# esp32_usb_c.net
KiCad netlist of a schematic drawn in Altium Designer
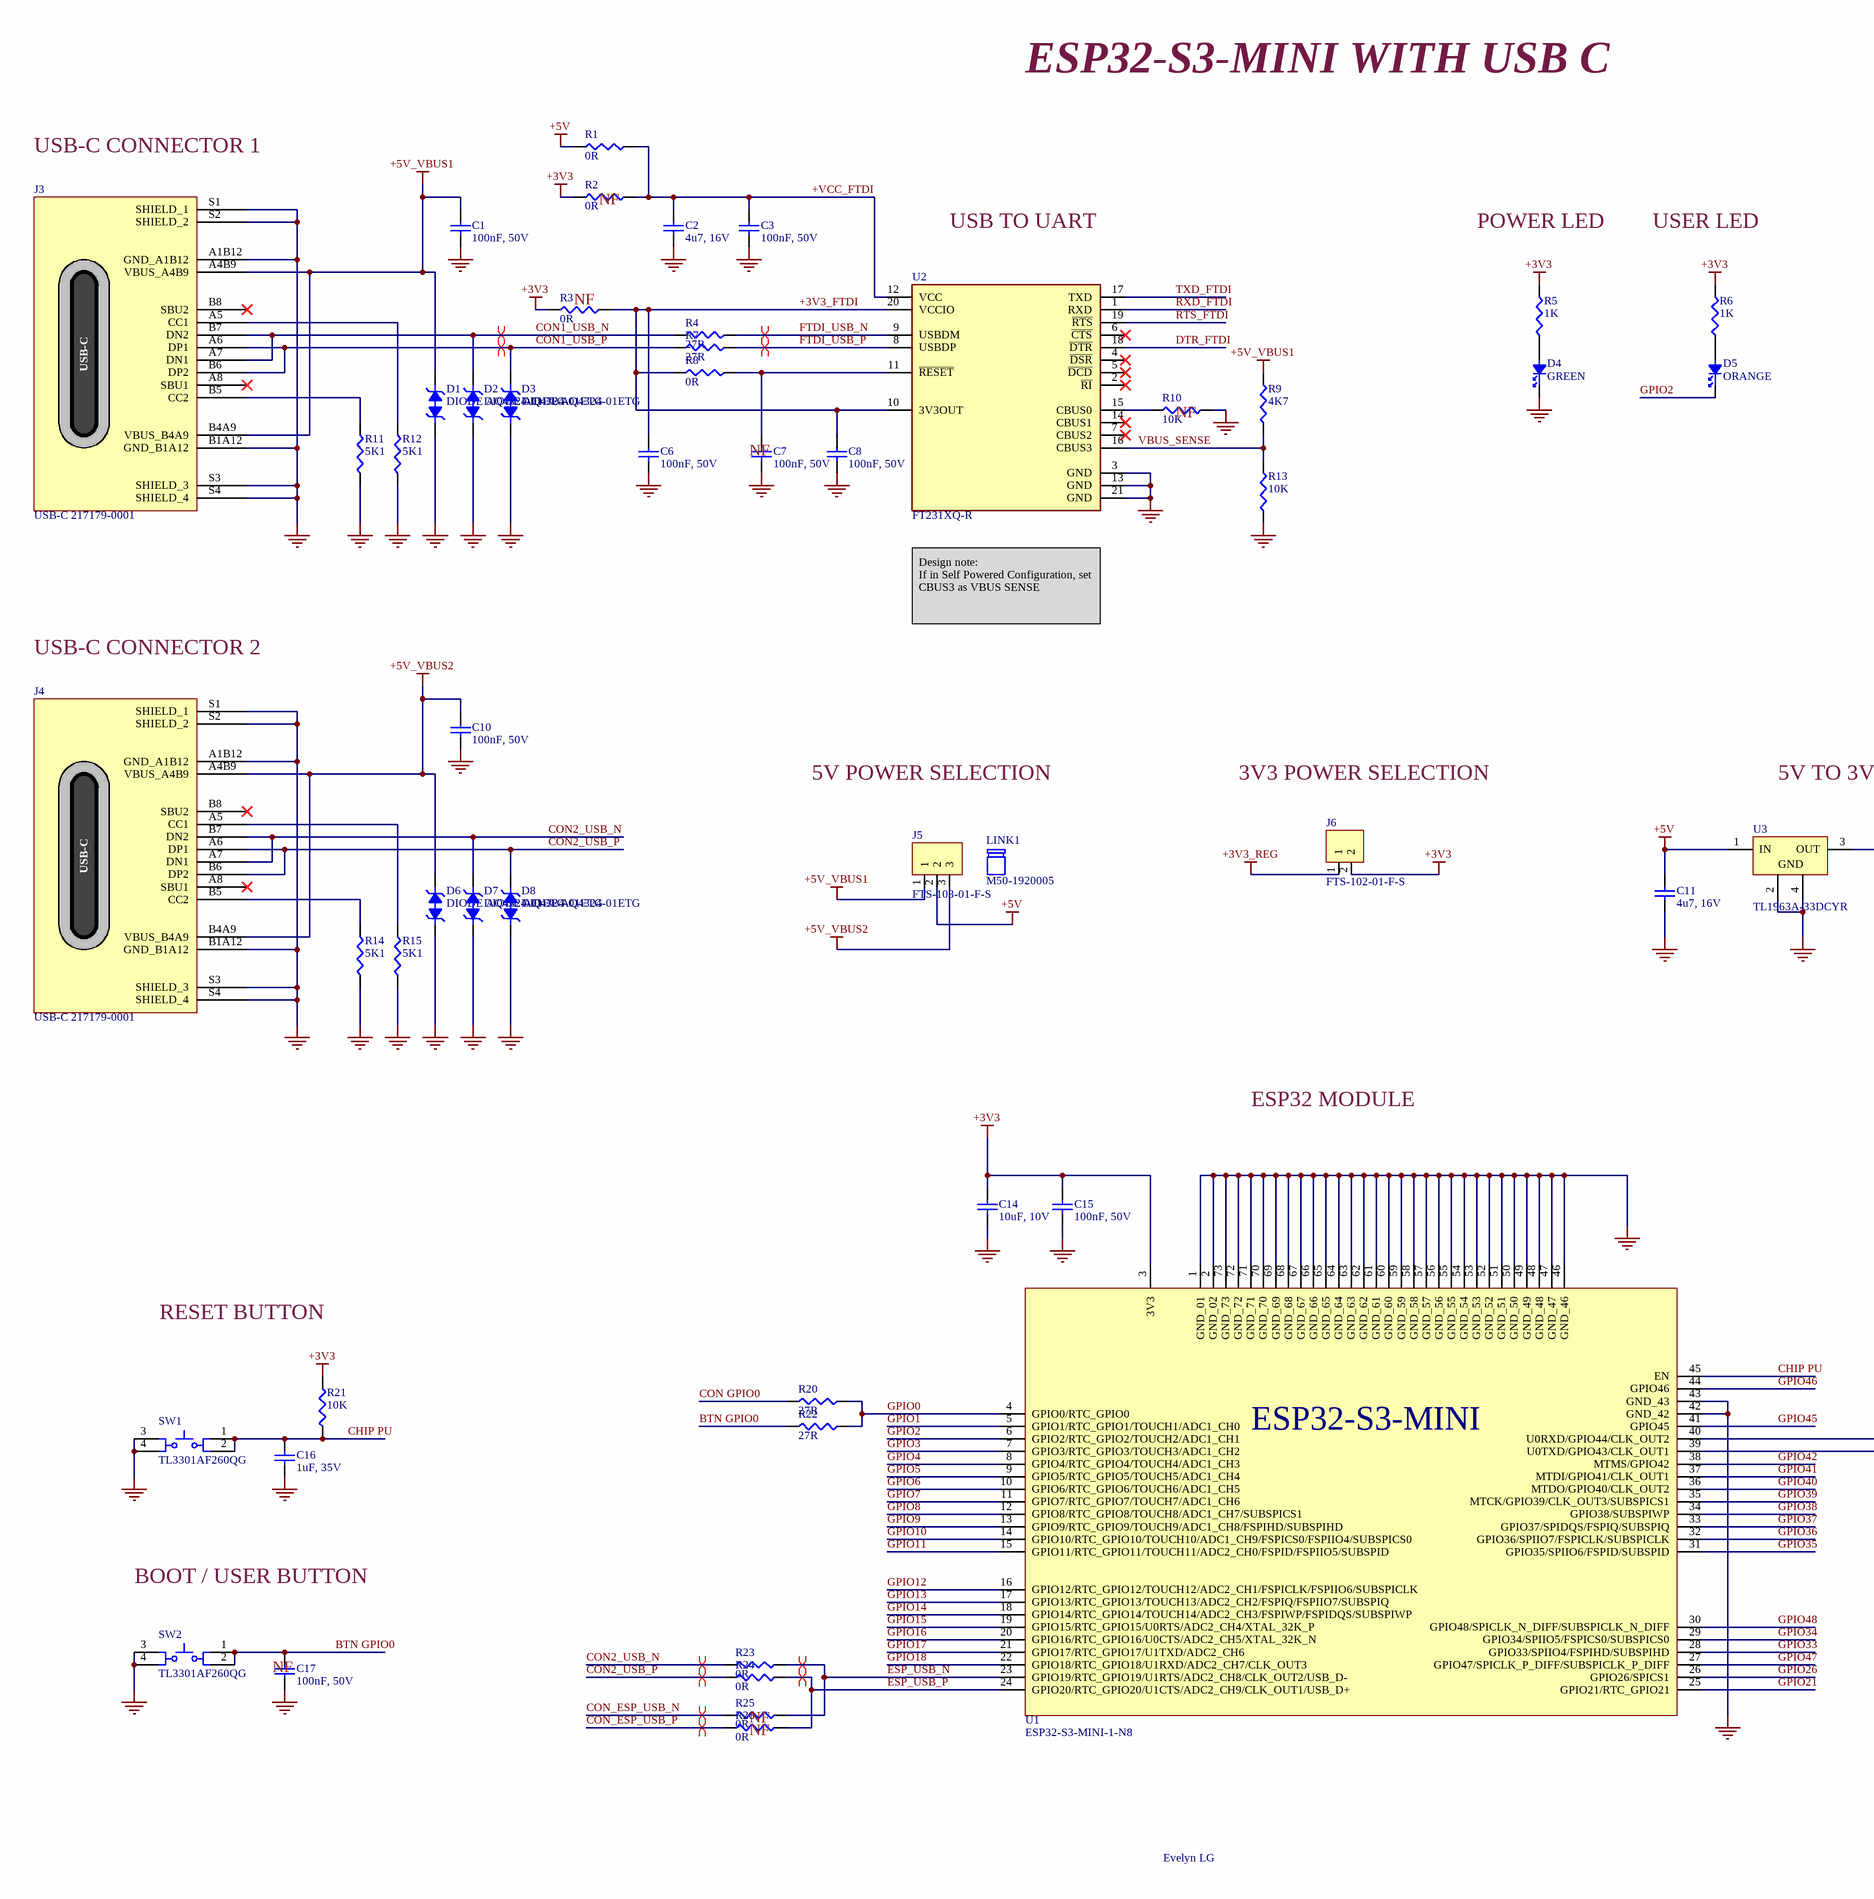
[diagram p0: esp32_usb_c.SchDoc, left]
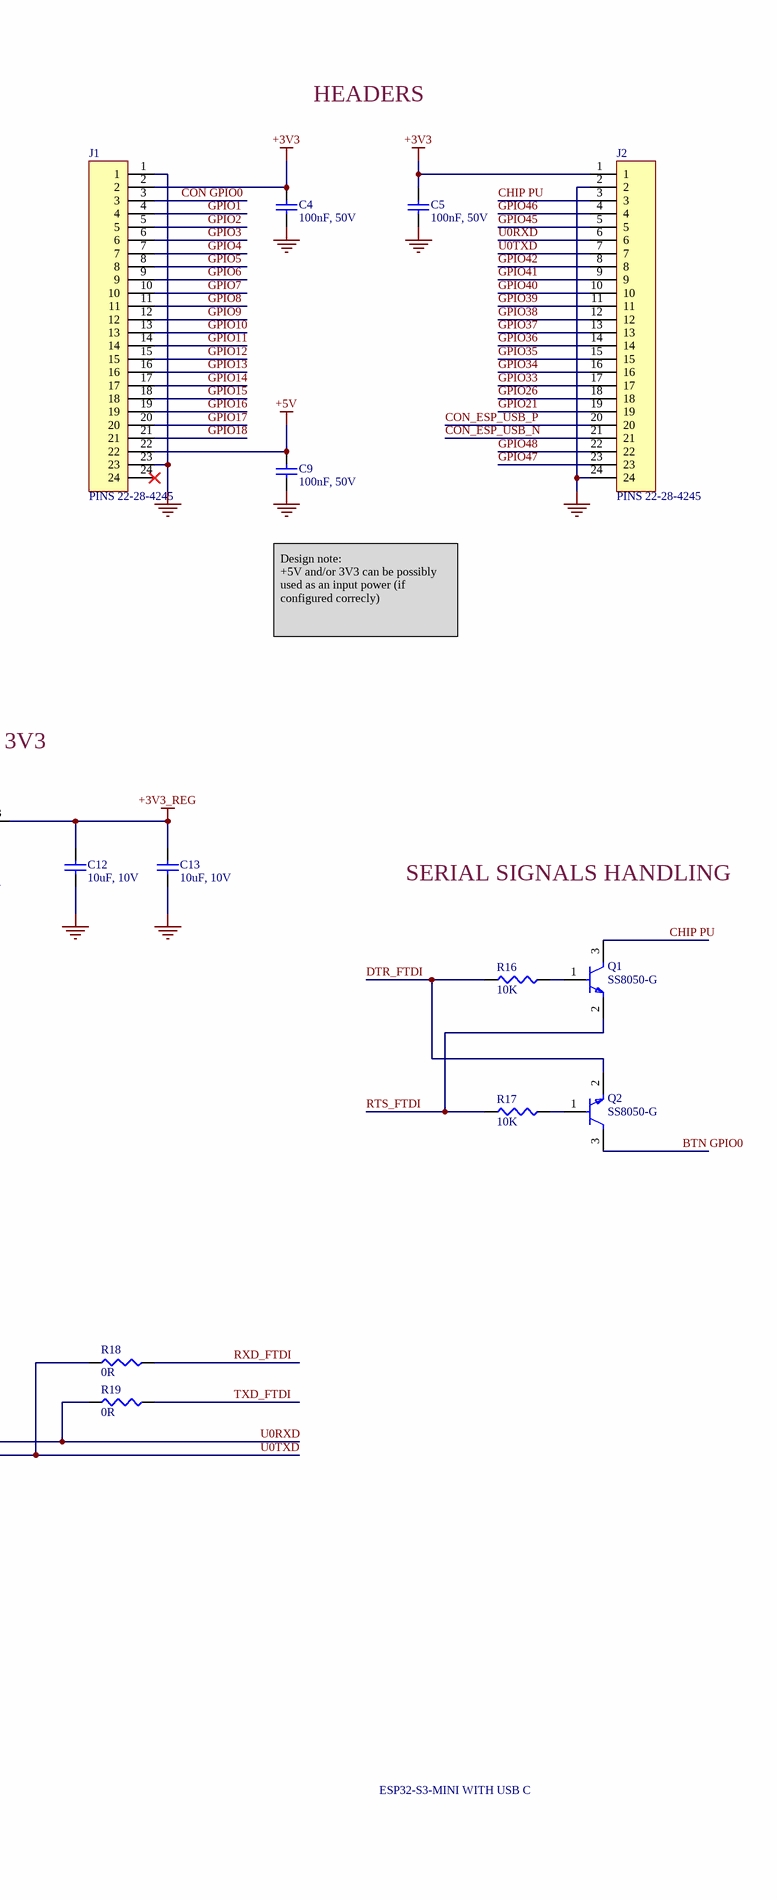
[diagram p1: esp32_usb_c.SchDoc, right]

(export (version "E")
  (design (tool "Eeschema 10.0.6"))
  (components
    (comp (ref "C1")
      (value "100nF, 50V")
      (footprint "CAPC1005X90N")
      (description "CAP CER 0.1UF 50V X7R 0402")
      (fields
        (field (name "MANUFACTURER") "Samsung Electro-Mechanics")
        (field (name "MANUFACTURER PART NUMBER") "CL05B104KB5NNNC")
      )
      (libsource (lib "Schlib") (part "CL05B104KB5NNNC"))
    )
    (comp (ref "C2")
      (value "4u7, 16V")
      (footprint "CAPC1005X90N")
      (description "CAP CER 4.7UF 16V X5R 0402")
      (fields
        (field (name "MANUFACTURER") "Samsung Electro-Mechanics")
        (field (name "MANUFACTURER PART NUMBER") "CL05A475MO5NUNC")
      )
      (libsource (lib "Schlib") (part "CL05A475MO5NUNC"))
    )
    (comp (ref "C3")
      (value "100nF, 50V")
      (footprint "CAPC1005X90N")
      (description "CAP CER 0.1UF 50V X7R 0402")
      (fields
        (field (name "MANUFACTURER") "Samsung Electro-Mechanics")
        (field (name "MANUFACTURER PART NUMBER") "CL05B104KB5NNNC")
      )
      (libsource (lib "Schlib") (part "CL05B104KB5NNNC"))
    )
    (comp (ref "C4")
      (value "100nF, 50V")
      (footprint "CAPC1005X90N")
      (description "CAP CER 0.1UF 50V X7R 0402")
      (fields
        (field (name "MANUFACTURER") "Samsung Electro-Mechanics")
        (field (name "MANUFACTURER PART NUMBER") "CL05B104KB5NNNC")
      )
      (libsource (lib "Schlib") (part "CL05B104KB5NNNC"))
    )
    (comp (ref "C5")
      (value "100nF, 50V")
      (footprint "CAPC1005X90N")
      (description "CAP CER 0.1UF 50V X7R 0402")
      (fields
        (field (name "MANUFACTURER") "Samsung Electro-Mechanics")
        (field (name "MANUFACTURER PART NUMBER") "CL05B104KB5NNNC")
      )
      (libsource (lib "Schlib") (part "CL05B104KB5NNNC"))
    )
    (comp (ref "C6")
      (value "100nF, 50V")
      (footprint "CAPC1005X90N")
      (description "CAP CER 0.1UF 50V X7R 0402")
      (fields
        (field (name "MANUFACTURER") "Samsung Electro-Mechanics")
        (field (name "MANUFACTURER PART NUMBER") "CL05B104KB5NNNC")
      )
      (libsource (lib "Schlib") (part "CL05B104KB5NNNC"))
    )
    (comp (ref "C7")
      (value "100nF, 50V")
      (footprint "CAPC1005X90N")
      (description "CAP CER 0.1UF 50V X7R 0402")
      (fields
        (field (name "MANUFACTURER") "Samsung Electro-Mechanics")
        (field (name "MANUFACTURER PART NUMBER") "CL05B104KB5NNNC")
      )
      (libsource (lib "Schlib") (part "CL05B104KB5NNNC"))
    )
    (comp (ref "C8")
      (value "100nF, 50V")
      (footprint "CAPC1005X90N")
      (description "CAP CER 0.1UF 50V X7R 0402")
      (fields
        (field (name "MANUFACTURER") "Samsung Electro-Mechanics")
        (field (name "MANUFACTURER PART NUMBER") "CL05B104KB5NNNC")
      )
      (libsource (lib "Schlib") (part "CL05B104KB5NNNC"))
    )
    (comp (ref "C9")
      (value "100nF, 50V")
      (footprint "CAPC1005X90N")
      (description "CAP CER 0.1UF 50V X7R 0402")
      (fields
        (field (name "MANUFACTURER") "Samsung Electro-Mechanics")
        (field (name "MANUFACTURER PART NUMBER") "CL05B104KB5NNNC")
      )
      (libsource (lib "Schlib") (part "CL05B104KB5NNNC"))
    )
    (comp (ref "C10")
      (value "100nF, 50V")
      (footprint "CAPC1005X90N")
      (description "CAP CER 0.1UF 50V X7R 0402")
      (fields
        (field (name "MANUFACTURER") "Samsung Electro-Mechanics")
        (field (name "MANUFACTURER PART NUMBER") "CL05B104KB5NNNC")
      )
      (libsource (lib "Schlib") (part "CL05B104KB5NNNC"))
    )
    (comp (ref "C11")
      (value "4u7, 16V")
      (footprint "CAPC1005X90N")
      (description "CAP CER 4.7UF 16V X5R 0402")
      (fields
        (field (name "MANUFACTURER") "Samsung Electro-Mechanics")
        (field (name "MANUFACTURER PART NUMBER") "CL05A475MO5NUNC")
      )
      (libsource (lib "Schlib") (part "CL05A475MO5NUNC"))
    )
    (comp (ref "C12")
      (value "10uF, 10V")
      (footprint "CAPC1005X90N")
      (description "CAP CER 10UF 10V X5R 0402")
      (fields
        (field (name "MANUFACTURER") "Samsung Electro-Mechanics")
        (field (name "MANUFACTURER PART NUMBER") "CL05A106MP8NUB8")
      )
      (libsource (lib "Schlib") (part "CL05A106MP8NUB8"))
    )
    (comp (ref "C13")
      (value "10uF, 10V")
      (footprint "CAPC1005X90N")
      (description "CAP CER 10UF 10V X5R 0402")
      (fields
        (field (name "MANUFACTURER") "Samsung Electro-Mechanics")
        (field (name "MANUFACTURER PART NUMBER") "CL05A106MP8NUB8")
      )
      (libsource (lib "Schlib") (part "CL05A106MP8NUB8"))
    )
    (comp (ref "C14")
      (value "10uF, 10V")
      (footprint "CAPC1005X90N")
      (description "CAP CER 10UF 10V X5R 0402")
      (fields
        (field (name "MANUFACTURER") "Samsung Electro-Mechanics")
        (field (name "MANUFACTURER PART NUMBER") "CL05A106MP8NUB8")
      )
      (libsource (lib "Schlib") (part "CL05A106MP8NUB8"))
    )
    (comp (ref "C15")
      (value "100nF, 50V")
      (footprint "CAPC1005X90N")
      (description "CAP CER 0.1UF 50V X7R 0402")
      (fields
        (field (name "MANUFACTURER") "Samsung Electro-Mechanics")
        (field (name "MANUFACTURER PART NUMBER") "CL05B104KB5NNNC")
      )
      (libsource (lib "Schlib") (part "CL05B104KB5NNNC"))
    )
    (comp (ref "C16")
      (value "1uF, 35V")
      (footprint "CAPC1005X90N")
      (description "CAP CER 1UF 10V X6S 0402")
      (fields
        (field (name "MANUFACTURER") "Samsung Electro-Mechanics")
        (field (name "MANUFACTURER PART NUMBER") "CL05X105KP5NNNC")
      )
      (libsource (lib "Schlib") (part "CL05X105KP5NNNC"))
    )
    (comp (ref "C17")
      (value "100nF, 50V")
      (footprint "CAPC1005X90N")
      (description "CAP CER 0.1UF 50V X7R 0402")
      (fields
        (field (name "MANUFACTURER") "Samsung Electro-Mechanics")
        (field (name "MANUFACTURER PART NUMBER") "CL05B104KB5NNNC")
      )
      (libsource (lib "Schlib") (part "CL05B104KB5NNNC"))
    )
    (comp (ref "D1")
      (value "DIODE AQ4324-01ETG")
      (footprint "SOD882")
      (description "DIODE ARRAYS 1CH 24V 12KV Bidir Tvs SOD882")
      (fields
        (field (name "MANUFACTURER") "Littelfuse")
        (field (name "MANUFACTURER PART NUMBER") "AQ4324-01ETG")
      )
      (libsource (lib "Schlib") (part "AQ4324-01ETG"))
    )
    (comp (ref "D2")
      (value "DIODE AQ4324-01ETG")
      (footprint "SOD882")
      (description "DIODE ARRAYS 1CH 24V 12KV Bidir Tvs SOD882")
      (fields
        (field (name "MANUFACTURER") "Littelfuse")
        (field (name "MANUFACTURER PART NUMBER") "AQ4324-01ETG")
      )
      (libsource (lib "Schlib") (part "AQ4324-01ETG"))
    )
    (comp (ref "D3")
      (value "DIODE AQ4324-01ETG")
      (footprint "SOD882")
      (description "DIODE ARRAYS 1CH 24V 12KV Bidir Tvs SOD882")
      (fields
        (field (name "MANUFACTURER") "Littelfuse")
        (field (name "MANUFACTURER PART NUMBER") "AQ4324-01ETG")
      )
      (libsource (lib "Schlib") (part "AQ4324-01ETG"))
    )
    (comp (ref "D4")
      (value "GREEN")
      (footprint "LED_0402_GREEN")
      (description "LED YLW-GRN 0402 SMD")
      (fields
        (field (name "MANUFACTURER") "Vishay")
        (field (name "MANUFACTURER PART NUMBER") "VLMG1500-GS08")
      )
      (libsource (lib "Schlib") (part "VLMG1500-GS08"))
    )
    (comp (ref "D5")
      (value "ORANGE")
      (footprint "LED_0402_ORANGE")
      (description "LED ORANGE 0402 SMD")
      (fields
        (field (name "MANUFACTURER") "Vishay")
        (field (name "MANUFACTURER PART NUMBER") "VLMO1500-GS08")
      )
      (libsource (lib "Schlib") (part "VLMO1500-GS08"))
    )
    (comp (ref "D6")
      (value "DIODE AQ4324-01ETG")
      (footprint "SOD882")
      (description "DIODE ARRAYS 1CH 24V 12KV Bidir Tvs SOD882")
      (fields
        (field (name "MANUFACTURER") "Littelfuse")
        (field (name "MANUFACTURER PART NUMBER") "AQ4324-01ETG")
      )
      (libsource (lib "Schlib") (part "AQ4324-01ETG"))
    )
    (comp (ref "D7")
      (value "DIODE AQ4324-01ETG")
      (footprint "SOD882")
      (description "DIODE ARRAYS 1CH 24V 12KV Bidir Tvs SOD882")
      (fields
        (field (name "MANUFACTURER") "Littelfuse")
        (field (name "MANUFACTURER PART NUMBER") "AQ4324-01ETG")
      )
      (libsource (lib "Schlib") (part "AQ4324-01ETG"))
    )
    (comp (ref "D8")
      (value "DIODE AQ4324-01ETG")
      (footprint "SOD882")
      (description "DIODE ARRAYS 1CH 24V 12KV Bidir Tvs SOD882")
      (fields
        (field (name "MANUFACTURER") "Littelfuse")
        (field (name "MANUFACTURER PART NUMBER") "AQ4324-01ETG")
      )
      (libsource (lib "Schlib") (part "AQ4324-01ETG"))
    )
    (comp (ref "J1")
      (value "PINS 22-28-4245")
      (footprint "HDR_1X24_2.54MM")
      (description "CONN HEADER VERT 24POS 2.54MM")
      (fields (field (name "MANUFACTURER") "Molex") (field (name "MANUFACTURER PART NUMBER") "22-28-4245"))
      (libsource (lib "Schlib") (part "22-28-4245"))
    )
    (comp (ref "J2")
      (value "PINS 22-28-4245")
      (footprint "HDR_1X24_2.54MM")
      (description "CONN HEADER VERT 24POS 2.54MM")
      (fields (field (name "MANUFACTURER") "Molex") (field (name "MANUFACTURER PART NUMBER") "22-28-4245"))
      (libsource (lib "") (part "22-28-4245_1"))
    )
    (comp (ref "J3")
      (value "USB-C 217179-0001")
      (footprint "FP-2171790001-MFG")
      (description "CONN RCP USB2.0 TYP C 24P SMD RA")
      (fields (field (name "MANUFACTURER") "Molex") (field (name "MANUFACTURER PART NUMBER") "217179-0001"))
      (libsource (lib "Schlib") (part "217179-0001"))
    )
    (comp (ref "J4")
      (value "USB-C 217179-0001")
      (footprint "FP-2171790001-MFG")
      (description "CONN RCP USB2.0 TYP C 24P SMD RA")
      (fields (field (name "MANUFACTURER") "Molex") (field (name "MANUFACTURER PART NUMBER") "217179-0001"))
      (libsource (lib "Schlib") (part "217179-0001"))
    )
    (comp (ref "J5")
      (value "FTS-103-01-F-S")
      (footprint "HDR_1X3_1.27MM")
      (description "CONN HEADER VERT 3POS 1.27MM")
      (fields (field (name "MANUFACTURER") "Samtec") (field (name "LCSC PART NUMBER") "C3333578"))
      (libsource (lib "Schlib") (part "FTS-103-01-F-S"))
    )
    (comp (ref "J6")
      (value "FTS-102-01-F-S")
      (footprint "HDR_1X2_1.27MM")
      (description "CONN HEADER VERT 2POS 1.27MM")
      (fields (field (name "MANUFACTURER") "Samtec") (field (name "LCSC PART NUMBER") "C6045317"))
      (libsource (lib "Schlib") (part "FTS-102-01-F-S"))
    )
    (comp (ref "LINK1")
      (value "M50-1920005")
      (description "CONN SHUNT 1.27MM RED")
      (fields (field (name "MANUFACTURER") "Harwin") (field (name "LCSC PART NUMBER") "C6985646"))
      (libsource (lib "Schlib") (part "M50-1920005"))
    )
    (comp (ref "Q1")
      (value "SS8050-G")
      (footprint "FP-SS8050-G-IPC_B")
      (description "TRANS NPN 25V 1.5A SOT-23-3/r")
      (fields (field (name "MANUFACTURER") "Comchip") (field (name "LCSC PART NUMBER") "C164886"))
      (libsource (lib "Schlib") (part "SS8050-G"))
    )
    (comp (ref "Q2")
      (value "SS8050-G")
      (footprint "FP-SS8050-G-IPC_B")
      (description "TRANS NPN 25V 1.5A SOT-23-3/r")
      (fields (field (name "MANUFACTURER") "Comchip") (field (name "LCSC PART NUMBER") "C164886"))
      (libsource (lib "Schlib") (part "SS8050-G"))
    )
    (comp (ref "R1")
      (value "0R")
      (footprint "RESC1005X37N")
      (description "RES 0 OHM JUMPER 1/16W 0402")
      (fields
        (field (name "MANUFACTURER") "Yageo Group")
        (field (name "MANUFACTURER PART NUMBER") "RC0402JR-070RL")
      )
      (libsource (lib "Schlib") (part "RC0402JR-070RL"))
    )
    (comp (ref "R2")
      (value "0R")
      (footprint "RESC1005X37N")
      (description "RES 0 OHM JUMPER 1/16W 0402")
      (fields
        (field (name "MANUFACTURER") "Yageo Group")
        (field (name "MANUFACTURER PART NUMBER") "RC0402JR-070RL")
      )
      (libsource (lib "Schlib") (part "RC0402JR-070RL"))
    )
    (comp (ref "R3")
      (value "0R")
      (footprint "RESC1005X37N")
      (description "RES 0 OHM JUMPER 1/16W 0402")
      (fields
        (field (name "MANUFACTURER") "Yageo Group")
        (field (name "MANUFACTURER PART NUMBER") "RC0402JR-070RL")
      )
      (libsource (lib "Schlib") (part "RC0402JR-070RL"))
    )
    (comp (ref "R4")
      (value "27R")
      (footprint "RESC1005X37N")
      (description "RES 27 OHM 1% 1/16W 0402")
      (fields
        (field (name "MANUFACTURER") "Yageo Group")
        (field (name "MANUFACTURER PART NUMBER") "RC0402FR-0727RL")
      )
      (libsource (lib "Schlib") (part "RC0402FR-0727RL"))
    )
    (comp (ref "R5")
      (value "1K")
      (footprint "RESC1005X37N")
      (description "RES 1K OHM 1% 1/16W 0402")
      (fields
        (field (name "MANUFACTURER") "Yageo Group")
        (field (name "MANUFACTURER PART NUMBER") "RC0402FR-071KL")
      )
      (libsource (lib "Schlib") (part "RC0402FR-071KL"))
    )
    (comp (ref "R6")
      (value "1K")
      (footprint "RESC1005X37N")
      (description "RES 1K OHM 1% 1/16W 0402")
      (fields
        (field (name "MANUFACTURER") "Yageo Group")
        (field (name "MANUFACTURER PART NUMBER") "RC0402FR-071KL")
      )
      (libsource (lib "Schlib") (part "RC0402FR-071KL"))
    )
    (comp (ref "R7")
      (value "27R")
      (footprint "RESC1005X37N")
      (description "RES 27 OHM 1% 1/16W 0402")
      (fields
        (field (name "MANUFACTURER") "Yageo Group")
        (field (name "MANUFACTURER PART NUMBER") "RC0402FR-0727RL")
      )
      (libsource (lib "Schlib") (part "RC0402FR-0727RL"))
    )
    (comp (ref "R8")
      (value "0R")
      (footprint "RESC1005X37N")
      (description "RES 0 OHM JUMPER 1/16W 0402")
      (fields
        (field (name "MANUFACTURER") "Yageo Group")
        (field (name "MANUFACTURER PART NUMBER") "RC0402JR-070RL")
      )
      (libsource (lib "Schlib") (part "RC0402JR-070RL"))
    )
    (comp (ref "R9")
      (value "4K7")
      (footprint "RESC1005X37N")
      (description "RES 4.7K OHM 1% 1/16W 0402")
      (fields
        (field (name "MANUFACTURER") "Yageo Group")
        (field (name "MANUFACTURER PART NUMBER") "RC0402FR-074K7L")
      )
      (libsource (lib "Schlib") (part "RC0402FR-074K7L"))
    )
    (comp (ref "R10")
      (value "10K")
      (footprint "RESC1005X37N")
      (description "Switch Tactile N.O. SPST Round Button Gull Wing 0.05A 12VDC 100000Cycles 1.96N SMD T/R")
      (fields
        (field (name "MANUFACTURER") "Yageo Group")
        (field (name "MANUFACTURER PART NUMBER") "RC0402FR-0710KL")
      )
      (libsource (lib "Schlib") (part "RC0402FR-0710KL"))
    )
    (comp (ref "R11")
      (value "5K1")
      (footprint "RESC1005X37N")
      (description "RES 5.1K OHM 1% 1/16W 0402")
      (fields
        (field (name "MANUFACTURER") "Yageo Group")
        (field (name "MANUFACTURER PART NUMBER") "RC0402FR-075K1L")
      )
      (libsource (lib "Schlib") (part "RC0402FR-075K1L"))
    )
    (comp (ref "R12")
      (value "5K1")
      (footprint "RESC1005X37N")
      (description "RES 5.1K OHM 1% 1/16W 0402")
      (fields
        (field (name "MANUFACTURER") "Yageo Group")
        (field (name "MANUFACTURER PART NUMBER") "RC0402FR-075K1L")
      )
      (libsource (lib "Schlib") (part "RC0402FR-075K1L"))
    )
    (comp (ref "R13")
      (value "10K")
      (footprint "RESC1005X37N")
      (description "Switch Tactile N.O. SPST Round Button Gull Wing 0.05A 12VDC 100000Cycles 1.96N SMD T/R")
      (fields
        (field (name "MANUFACTURER") "Yageo Group")
        (field (name "MANUFACTURER PART NUMBER") "RC0402FR-0710KL")
      )
      (libsource (lib "Schlib") (part "RC0402FR-0710KL"))
    )
    (comp (ref "R14")
      (value "5K1")
      (footprint "RESC1005X37N")
      (description "RES 5.1K OHM 1% 1/16W 0402")
      (fields
        (field (name "MANUFACTURER") "Yageo Group")
        (field (name "MANUFACTURER PART NUMBER") "RC0402FR-075K1L")
      )
      (libsource (lib "Schlib") (part "RC0402FR-075K1L"))
    )
    (comp (ref "R15")
      (value "5K1")
      (footprint "RESC1005X37N")
      (description "RES 5.1K OHM 1% 1/16W 0402")
      (fields
        (field (name "MANUFACTURER") "Yageo Group")
        (field (name "MANUFACTURER PART NUMBER") "RC0402FR-075K1L")
      )
      (libsource (lib "Schlib") (part "RC0402FR-075K1L"))
    )
    (comp (ref "R16")
      (value "10K")
      (footprint "RESC1005X37N")
      (description "Switch Tactile N.O. SPST Round Button Gull Wing 0.05A 12VDC 100000Cycles 1.96N SMD T/R")
      (fields
        (field (name "MANUFACTURER") "Yageo Group")
        (field (name "MANUFACTURER PART NUMBER") "RC0402FR-0710KL")
      )
      (libsource (lib "Schlib") (part "RC0402FR-0710KL"))
    )
    (comp (ref "R17")
      (value "10K")
      (footprint "RESC1005X37N")
      (description "Switch Tactile N.O. SPST Round Button Gull Wing 0.05A 12VDC 100000Cycles 1.96N SMD T/R")
      (fields
        (field (name "MANUFACTURER") "Yageo Group")
        (field (name "MANUFACTURER PART NUMBER") "RC0402FR-0710KL")
      )
      (libsource (lib "Schlib") (part "RC0402FR-0710KL"))
    )
    (comp (ref "R18")
      (value "0R")
      (footprint "RESC1005X37N")
      (description "RES 0 OHM JUMPER 1/16W 0402")
      (fields
        (field (name "MANUFACTURER") "Yageo Group")
        (field (name "MANUFACTURER PART NUMBER") "RC0402JR-070RL")
      )
      (libsource (lib "Schlib") (part "RC0402JR-070RL"))
    )
    (comp (ref "R19")
      (value "0R")
      (footprint "RESC1005X37N")
      (description "RES 0 OHM JUMPER 1/16W 0402")
      (fields
        (field (name "MANUFACTURER") "Yageo Group")
        (field (name "MANUFACTURER PART NUMBER") "RC0402JR-070RL")
      )
      (libsource (lib "Schlib") (part "RC0402JR-070RL"))
    )
    (comp (ref "R20")
      (value "27R")
      (footprint "RESC1005X37N")
      (description "RES 27 OHM 1% 1/16W 0402")
      (fields
        (field (name "MANUFACTURER") "Yageo Group")
        (field (name "MANUFACTURER PART NUMBER") "RC0402FR-0727RL")
      )
      (libsource (lib "Schlib") (part "RC0402FR-0727RL"))
    )
    (comp (ref "R21")
      (value "10K")
      (footprint "RESC1005X37N")
      (description "Switch Tactile N.O. SPST Round Button Gull Wing 0.05A 12VDC 100000Cycles 1.96N SMD T/R")
      (fields
        (field (name "MANUFACTURER") "Yageo Group")
        (field (name "MANUFACTURER PART NUMBER") "RC0402FR-0710KL")
      )
      (libsource (lib "Schlib") (part "RC0402FR-0710KL"))
    )
    (comp (ref "R22")
      (value "27R")
      (footprint "RESC1005X37N")
      (description "RES 27 OHM 1% 1/16W 0402")
      (fields
        (field (name "MANUFACTURER") "Yageo Group")
        (field (name "MANUFACTURER PART NUMBER") "RC0402FR-0727RL")
      )
      (libsource (lib "Schlib") (part "RC0402FR-0727RL"))
    )
    (comp (ref "R23")
      (value "0R")
      (footprint "RESC1005X37N")
      (description "RES 0 OHM JUMPER 1/16W 0402")
      (fields
        (field (name "MANUFACTURER") "Yageo Group")
        (field (name "MANUFACTURER PART NUMBER") "RC0402JR-070RL")
      )
      (libsource (lib "Schlib") (part "RC0402JR-070RL"))
    )
    (comp (ref "R24")
      (value "0R")
      (footprint "RESC1005X37N")
      (description "RES 0 OHM JUMPER 1/16W 0402")
      (fields
        (field (name "MANUFACTURER") "Yageo Group")
        (field (name "MANUFACTURER PART NUMBER") "RC0402JR-070RL")
      )
      (libsource (lib "Schlib") (part "RC0402JR-070RL"))
    )
    (comp (ref "R25")
      (value "0R")
      (footprint "RESC1005X37N")
      (description "RES 0 OHM JUMPER 1/16W 0402")
      (fields
        (field (name "MANUFACTURER") "Yageo Group")
        (field (name "MANUFACTURER PART NUMBER") "RC0402JR-070RL")
      )
      (libsource (lib "Schlib") (part "RC0402JR-070RL"))
    )
    (comp (ref "R26")
      (value "0R")
      (footprint "RESC1005X37N")
      (description "RES 0 OHM JUMPER 1/16W 0402")
      (fields
        (field (name "MANUFACTURER") "Yageo Group")
        (field (name "MANUFACTURER PART NUMBER") "RC0402JR-070RL")
      )
      (libsource (lib "Schlib") (part "RC0402JR-070RL"))
    )
    (comp (ref "SW1")
      (value "TL3301AF260QG")
      (footprint "ESWI-TL3301AF260QG_V")
      (description "SWITCH TACTILE SPST-NO 0.05A 12V")
      (fields (field (name "MANUFACTURER") "E-Switch") (field (name "LCSC PART #") "C273496"))
      (libsource (lib "Schlib") (part "TL3301AF260QG"))
    )
    (comp (ref "SW2")
      (value "TL3301AF260QG")
      (footprint "ESWI-TL3301AF260QG_V")
      (description "SWITCH TACTILE SPST-NO 0.05A 12V")
      (fields (field (name "MANUFACTURER") "E-Switch") (field (name "LCSC PART #") "C273496"))
      (libsource (lib "Schlib") (part "TL3301AF260QG"))
    )
    (comp (ref "U1")
      (value "ESP32-S3-MINI-1-N8")
      (footprint "XCVR_ESP32-S3-MINI-1-N8")
      (description "20.5dBm ESP32-S3FN8 Chip 2.4GHz SMD WiFi Modules ROHS")
      (fields (field (name "MANUFACTURER") "Espressif Systems") (field (name "LCSC PART NUMBER") "C2913206"))
      (libsource (lib "Schlib") (part "ESP32-S3-MINI-1-N8"))
    )
    (comp (ref "U2")
      (value "FT231XQ-R")
      (footprint "FP-QFN-20-IPC_B")
      (description "IC USB SERIAL FULL UART 20QFN")
      (fields (field (name "MANUFACTURER") "FTDI") (field (name "LCSC PART NUMBER") "C132159"))
      (libsource (lib "Schlib") (part "FT231XQ-R"))
    )
    (comp (ref "U3")
      (value "TL1963A-33DCYR")
      (footprint "DCY0004A_N")
      (description "IC REG LIN 3.3V 1.5A SOT-223-4")
      (fields (field (name "MANUFACTURER") "Texas Instruments") (field (name "LCSC PART NUMBER") "C181262"))
      (libsource (lib "Schlib") (part "TL1963A-33DCYR"))
    )
  )
  (nets
    (net (code "1") (name "+3V3") (class "Default")
      (node (ref "C14") (pin "2") (pinfunction "2_2") (pintype "passive"))
      (node (ref "C15") (pin "2") (pinfunction "2_2") (pintype "passive"))
      (node (ref "C4") (pin "2") (pinfunction "2_2") (pintype "passive"))
      (node (ref "C5") (pin "2") (pinfunction "2_2") (pintype "passive"))
      (node (ref "J1") (pin "2") (pinfunction "2_2") (pintype "passive"))
      (node (ref "J2") (pin "1") (pinfunction "1_1") (pintype "passive"))
      (node (ref "J6") (pin "2") (pinfunction "2_2") (pintype "passive"))
      (node (ref "R2") (pin "1") (pinfunction "1_1") (pintype "passive"))
      (node (ref "R21") (pin "2") (pinfunction "2_2") (pintype "passive"))
      (node (ref "R3") (pin "1") (pinfunction "1_1") (pintype "passive"))
      (node (ref "R5") (pin "2") (pinfunction "2_2") (pintype "passive"))
      (node (ref "R6") (pin "2") (pinfunction "2_2") (pintype "passive"))
      (node (ref "U1") (pin "3") (pinfunction "3V3_3") (pintype "passive"))
    )
    (net (code "2") (name "+3V3_REG") (class "Default")
      (node (ref "C12") (pin "2") (pinfunction "2_2") (pintype "passive"))
      (node (ref "C13") (pin "2") (pinfunction "2_2") (pintype "passive"))
      (node (ref "J6") (pin "1") (pinfunction "1_1") (pintype "passive"))
      (node (ref "U3") (pin "3") (pinfunction "OUT_3") (pintype "power_in"))
    )
    (net (code "3") (name "+5V") (class "Default")
      (node (ref "C11") (pin "2") (pinfunction "2_2") (pintype "passive"))
      (node (ref "C9") (pin "2") (pinfunction "2_2") (pintype "passive"))
      (node (ref "J1") (pin "22") (pinfunction "22_22") (pintype "passive"))
      (node (ref "J5") (pin "2") (pinfunction "2_2") (pintype "passive"))
      (node (ref "R1") (pin "1") (pinfunction "1_1") (pintype "passive"))
      (node (ref "U3") (pin "1") (pinfunction "IN_1") (pintype "power_in"))
    )
    (net (code "4") (name "+5V_VBUS1") (class "Default")
      (node (ref "C1") (pin "2") (pinfunction "2_2") (pintype "passive"))
      (node (ref "D1") (pin "2") (pinfunction "2_2") (pintype "passive"))
      (node (ref "J3") (pin "A4B9") (pinfunction "VBUS_A4B9_A4B9") (pintype "passive"))
      (node (ref "J3") (pin "B4A9") (pinfunction "VBUS_B4A9_B4A9") (pintype "passive"))
      (node (ref "J5") (pin "1") (pinfunction "1_1") (pintype "passive"))
      (node (ref "R9") (pin "2") (pinfunction "2_2") (pintype "passive"))
    )
    (net (code "5") (name "+5V_VBUS2") (class "Default")
      (node (ref "C10") (pin "2") (pinfunction "2_2") (pintype "passive"))
      (node (ref "D6") (pin "2") (pinfunction "2_2") (pintype "passive"))
      (node (ref "J4") (pin "A4B9") (pinfunction "VBUS_A4B9_A4B9") (pintype "passive"))
      (node (ref "J4") (pin "B4A9") (pinfunction "VBUS_B4A9_B4A9") (pintype "passive"))
      (node (ref "J5") (pin "3") (pinfunction "3_3") (pintype "passive"))
    )
    (net (code "6") (name "/+3V3_FTDI") (class "Default")
      (node (ref "C6") (pin "2") (pinfunction "2_2") (pintype "passive"))
      (node (ref "C8") (pin "2") (pinfunction "2_2") (pintype "passive"))
      (node (ref "R3") (pin "2") (pinfunction "2_2") (pintype "passive"))
      (node (ref "R8") (pin "1") (pinfunction "1_1") (pintype "passive"))
      (node (ref "U2") (pin "10") (pinfunction "3V3OUT_10") (pintype "passive"))
      (node (ref "U2") (pin "20") (pinfunction "VCCIO_20") (pintype "passive"))
    )
    (net (code "7") (name "/+VCC_FTDI") (class "Default")
      (node (ref "C2") (pin "2") (pinfunction "2_2") (pintype "passive"))
      (node (ref "C3") (pin "2") (pinfunction "2_2") (pintype "passive"))
      (node (ref "R1") (pin "2") (pinfunction "2_2") (pintype "passive"))
      (node (ref "R2") (pin "2") (pinfunction "2_2") (pintype "passive"))
      (node (ref "U2") (pin "12") (pinfunction "VCC_12") (pintype "passive"))
    )
    (net (code "8") (name "/BTN GPIO0") (class "Default")
      (node (ref "C17") (pin "2") (pinfunction "2_2") (pintype "passive"))
      (node (ref "Q2") (pin "3") (pinfunction "C_3") (pintype "passive"))
      (node (ref "R22") (pin "1") (pinfunction "1_1") (pintype "passive"))
      (node (ref "SW2") (pin "1") (pinfunction "1_1") (pintype "passive"))
      (node (ref "SW2") (pin "2") (pinfunction "2_2") (pintype "passive"))
    )
    (net (code "9") (name "/CHIP PU") (class "Default")
      (node (ref "C16") (pin "2") (pinfunction "2_2") (pintype "passive"))
      (node (ref "J2") (pin "3") (pinfunction "3_3") (pintype "passive"))
      (node (ref "Q1") (pin "3") (pinfunction "C_3") (pintype "passive"))
      (node (ref "R21") (pin "1") (pinfunction "1_1") (pintype "passive"))
      (node (ref "SW1") (pin "1") (pinfunction "1_1") (pintype "passive"))
      (node (ref "SW1") (pin "2") (pinfunction "2_2") (pintype "passive"))
      (node (ref "U1") (pin "45") (pinfunction "EN_45") (pintype "passive"))
    )
    (net (code "10") (name "/CON GPIO0") (class "Default")
      (node (ref "J1") (pin "3") (pinfunction "3_3") (pintype "passive"))
      (node (ref "R20") (pin "1") (pinfunction "1_1") (pintype "passive"))
    )
    (net (code "11") (name "/CON1_USB_N") (class "Default")
      (node (ref "D2") (pin "2") (pinfunction "2_2") (pintype "passive"))
      (node (ref "J3") (pin "A7") (pinfunction "DN1_A7") (pintype "passive"))
      (node (ref "J3") (pin "B7") (pinfunction "DN2_B7") (pintype "passive"))
      (node (ref "R4") (pin "1") (pinfunction "1_1") (pintype "passive"))
    )
    (net (code "12") (name "/CON1_USB_P") (class "Default")
      (node (ref "D3") (pin "2") (pinfunction "2_2") (pintype "passive"))
      (node (ref "J3") (pin "A6") (pinfunction "DP1_A6") (pintype "passive"))
      (node (ref "J3") (pin "B6") (pinfunction "DP2_B6") (pintype "passive"))
      (node (ref "R7") (pin "1") (pinfunction "1_1") (pintype "passive"))
    )
    (net (code "13") (name "/CON2_USB_N") (class "Default")
      (node (ref "D7") (pin "2") (pinfunction "2_2") (pintype "passive"))
      (node (ref "J4") (pin "A7") (pinfunction "DN1_A7") (pintype "passive"))
      (node (ref "J4") (pin "B7") (pinfunction "DN2_B7") (pintype "passive"))
      (node (ref "R23") (pin "1") (pinfunction "1_1") (pintype "passive"))
    )
    (net (code "14") (name "/CON2_USB_P") (class "Default")
      (node (ref "D8") (pin "2") (pinfunction "2_2") (pintype "passive"))
      (node (ref "J4") (pin "A6") (pinfunction "DP1_A6") (pintype "passive"))
      (node (ref "J4") (pin "B6") (pinfunction "DP2_B6") (pintype "passive"))
      (node (ref "R24") (pin "1") (pinfunction "1_1") (pintype "passive"))
    )
    (net (code "15") (name "/CON_ESP_USB_N") (class "Default")
      (node (ref "J2") (pin "21") (pinfunction "21_21") (pintype "passive"))
      (node (ref "R25") (pin "1") (pinfunction "1_1") (pintype "passive"))
    )
    (net (code "16") (name "/CON_ESP_USB_P") (class "Default")
      (node (ref "J2") (pin "20") (pinfunction "20_20") (pintype "passive"))
      (node (ref "R26") (pin "1") (pinfunction "1_1") (pintype "passive"))
    )
    (net (code "17") (name "/DTR_FTDI") (class "Default")
      (node (ref "Q2") (pin "2") (pinfunction "E_2") (pintype "passive"))
      (node (ref "R16") (pin "1") (pinfunction "1_1") (pintype "passive"))
      (node (ref "U2") (pin "18") (pinfunction "~{DTR}_18") (pintype "passive"))
    )
    (net (code "18") (name "/ESP_USB_N") (class "Default")
      (node (ref "R23") (pin "2") (pinfunction "2_2") (pintype "passive"))
      (node (ref "R25") (pin "2") (pinfunction "2_2") (pintype "passive"))
      (node (ref "U1") (pin "23") (pinfunction "GPIO19/RTC_GPIO19/U1RTS/ADC2_CH8/CLK_OUT2/USB_D-_23") (pintype "passive"))
    )
    (net (code "19") (name "/ESP_USB_P") (class "Default")
      (node (ref "R24") (pin "2") (pinfunction "2_2") (pintype "passive"))
      (node (ref "R26") (pin "2") (pinfunction "2_2") (pintype "passive"))
      (node (ref "U1") (pin "24") (pinfunction "GPIO20/RTC_GPIO20/U1CTS/ADC2_CH9/CLK_OUT1/USB_D+_24") (pintype "passive"))
    )
    (net (code "20") (name "/FTDI_USB_N") (class "Default")
      (node (ref "R4") (pin "2") (pinfunction "2_2") (pintype "passive"))
      (node (ref "U2") (pin "9") (pinfunction "USBDM_9") (pintype "passive"))
    )
    (net (code "21") (name "/FTDI_USB_P") (class "Default")
      (node (ref "R7") (pin "2") (pinfunction "2_2") (pintype "passive"))
      (node (ref "U2") (pin "8") (pinfunction "USBDP_8") (pintype "passive"))
    )
    (net (code "22") (name "/GPIO0") (class "Default")
      (node (ref "R20") (pin "2") (pinfunction "2_2") (pintype "passive"))
      (node (ref "R22") (pin "2") (pinfunction "2_2") (pintype "passive"))
      (node (ref "U1") (pin "4") (pinfunction "GPIO0/RTC_GPIO0_4") (pintype "passive"))
    )
    (net (code "23") (name "/GPIO1") (class "Default")
      (node (ref "J1") (pin "4") (pinfunction "4_4") (pintype "passive"))
      (node (ref "U1") (pin "5") (pinfunction "GPIO1/RTC_GPIO1/TOUCH1/ADC1_CH0_5") (pintype "passive"))
    )
    (net (code "24") (name "/GPIO2") (class "Default")
      (node (ref "D5") (pin "1") (pinfunction "1_1") (pintype "passive"))
      (node (ref "J1") (pin "5") (pinfunction "5_5") (pintype "passive"))
      (node (ref "U1") (pin "6") (pinfunction "GPIO2/RTC_GPIO2/TOUCH2/ADC1_CH1_6") (pintype "passive"))
    )
    (net (code "25") (name "/GPIO3") (class "Default")
      (node (ref "J1") (pin "6") (pinfunction "6_6") (pintype "passive"))
      (node (ref "U1") (pin "7") (pinfunction "GPIO3/RTC_GPIO3/TOUCH3/ADC1_CH2_7") (pintype "passive"))
    )
    (net (code "26") (name "/GPIO4") (class "Default")
      (node (ref "J1") (pin "7") (pinfunction "7_7") (pintype "passive"))
      (node (ref "U1") (pin "8") (pinfunction "GPIO4/RTC_GPIO4/TOUCH4/ADC1_CH3_8") (pintype "passive"))
    )
    (net (code "27") (name "/GPIO5") (class "Default")
      (node (ref "J1") (pin "8") (pinfunction "8_8") (pintype "passive"))
      (node (ref "U1") (pin "9") (pinfunction "GPIO5/RTC_GPIO5/TOUCH5/ADC1_CH4_9") (pintype "passive"))
    )
    (net (code "28") (name "/GPIO6") (class "Default")
      (node (ref "J1") (pin "9") (pinfunction "9_9") (pintype "passive"))
      (node (ref "U1") (pin "10") (pinfunction "GPIO6/RTC_GPIO6/TOUCH6/ADC1_CH5_10") (pintype "passive"))
    )
    (net (code "29") (name "/GPIO7") (class "Default")
      (node (ref "J1") (pin "10") (pinfunction "10_10") (pintype "passive"))
      (node (ref "U1") (pin "11") (pinfunction "GPIO7/RTC_GPIO7/TOUCH7/ADC1_CH6_11") (pintype "passive"))
    )
    (net (code "30") (name "/GPIO8") (class "Default")
      (node (ref "J1") (pin "11") (pinfunction "11_11") (pintype "passive"))
      (node (ref "U1") (pin "12") (pinfunction "GPIO8/RTC_GPIO8/TOUCH8/ADC1_CH7/SUBSPICS1_12") (pintype "passive"))
    )
    (net (code "31") (name "/GPIO9") (class "Default")
      (node (ref "J1") (pin "12") (pinfunction "12_12") (pintype "passive"))
      (node (ref "U1") (pin "13") (pinfunction "GPIO9/RTC_GPIO9/TOUCH9/ADC1_CH8/FSPIHD/SUBSPIHD_13") (pintype "passive"))
    )
    (net (code "32") (name "/GPIO10") (class "Default")
      (node (ref "J1") (pin "13") (pinfunction "13_13") (pintype "passive"))
      (node (ref "U1") (pin "14") (pinfunction "GPIO10/RTC_GPIO10/TOUCH10/ADC1_CH9/FSPICS0/FSPIIO4/SUBSPICS0_14") (pintype "passive"))
    )
    (net (code "33") (name "/GPIO11") (class "Default")
      (node (ref "J1") (pin "14") (pinfunction "14_14") (pintype "passive"))
      (node (ref "U1") (pin "15") (pinfunction "GPIO11/RTC_GPIO11/TOUCH11/ADC2_CH0/FSPID/FSPIIO5/SUBSPID_15") (pintype "passive"))
    )
    (net (code "34") (name "/GPIO12") (class "Default")
      (node (ref "J1") (pin "15") (pinfunction "15_15") (pintype "passive"))
      (node (ref "U1") (pin "16") (pinfunction "GPIO12/RTC_GPIO12/TOUCH12/ADC2_CH1/FSPICLK/FSPIIO6/SUBSPICLK_16") (pintype "passive"))
    )
    (net (code "35") (name "/GPIO13") (class "Default")
      (node (ref "J1") (pin "16") (pinfunction "16_16") (pintype "passive"))
      (node (ref "U1") (pin "17") (pinfunction "GPIO13/RTC_GPIO13/TOUCH13/ADC2_CH2/FSPIQ/FSPIIO7/SUBSPIQ_17") (pintype "passive"))
    )
    (net (code "36") (name "/GPIO14") (class "Default")
      (node (ref "J1") (pin "17") (pinfunction "17_17") (pintype "passive"))
      (node (ref "U1") (pin "18") (pinfunction "GPIO14/RTC_GPIO14/TOUCH14/ADC2_CH3/FSPIWP/FSPIDQS/SUBSPIWP_18") (pintype "passive"))
    )
    (net (code "37") (name "/GPIO15") (class "Default")
      (node (ref "J1") (pin "18") (pinfunction "18_18") (pintype "passive"))
      (node (ref "U1") (pin "19") (pinfunction "GPIO15/RTC_GPIO15/U0RTS/ADC2_CH4/XTAL_32K_P_19") (pintype "passive"))
    )
    (net (code "38") (name "/GPIO16") (class "Default")
      (node (ref "J1") (pin "19") (pinfunction "19_19") (pintype "passive"))
      (node (ref "U1") (pin "20") (pinfunction "GPIO16/RTC_GPIO16/U0CTS/ADC2_CH5/XTAL_32K_N_20") (pintype "passive"))
    )
    (net (code "39") (name "/GPIO17") (class "Default")
      (node (ref "J1") (pin "20") (pinfunction "20_20") (pintype "passive"))
      (node (ref "U1") (pin "21") (pinfunction "GPIO17/RTC_GPIO17/U1TXD/ADC2_CH6_21") (pintype "passive"))
    )
    (net (code "40") (name "/GPIO18") (class "Default")
      (node (ref "J1") (pin "21") (pinfunction "21_21") (pintype "passive"))
      (node (ref "U1") (pin "22") (pinfunction "GPIO18/RTC_GPIO18/U1RXD/ADC2_CH7/CLK_OUT3_22") (pintype "passive"))
    )
    (net (code "41") (name "/GPIO21") (class "Default")
      (node (ref "J2") (pin "19") (pinfunction "19_19") (pintype "passive"))
      (node (ref "U1") (pin "25") (pinfunction "GPIO21/RTC_GPIO21_25") (pintype "passive"))
    )
    (net (code "42") (name "/GPIO26") (class "Default")
      (node (ref "J2") (pin "18") (pinfunction "18_18") (pintype "passive"))
      (node (ref "U1") (pin "26") (pinfunction "GPIO26/SPICS1_26") (pintype "passive"))
    )
    (net (code "43") (name "/GPIO33") (class "Default")
      (node (ref "J2") (pin "17") (pinfunction "17_17") (pintype "passive"))
      (node (ref "U1") (pin "28") (pinfunction "GPIO33/SPIIO4/FSPIHD/SUBSPIHD_28") (pintype "passive"))
    )
    (net (code "44") (name "/GPIO34") (class "Default")
      (node (ref "J2") (pin "16") (pinfunction "16_16") (pintype "passive"))
      (node (ref "U1") (pin "29") (pinfunction "GPIO34/SPIIO5/FSPICS0/SUBSPICS0_29") (pintype "passive"))
    )
    (net (code "45") (name "/GPIO35") (class "Default")
      (node (ref "J2") (pin "15") (pinfunction "15_15") (pintype "passive"))
      (node (ref "U1") (pin "31") (pinfunction "GPIO35/SPIIO6/FSPID/SUBSPID_31") (pintype "passive"))
    )
    (net (code "46") (name "/GPIO36") (class "Default")
      (node (ref "J2") (pin "14") (pinfunction "14_14") (pintype "passive"))
      (node (ref "U1") (pin "32") (pinfunction "GPIO36/SPIIO7/FSPICLK/SUBSPICLK_32") (pintype "passive"))
    )
    (net (code "47") (name "/GPIO37") (class "Default")
      (node (ref "J2") (pin "13") (pinfunction "13_13") (pintype "passive"))
      (node (ref "U1") (pin "33") (pinfunction "GPIO37/SPIDQS/FSPIQ/SUBSPIQ_33") (pintype "passive"))
    )
    (net (code "48") (name "/GPIO38") (class "Default")
      (node (ref "J2") (pin "12") (pinfunction "12_12") (pintype "passive"))
      (node (ref "U1") (pin "34") (pinfunction "GPIO38/SUBSPIWP_34") (pintype "passive"))
    )
    (net (code "49") (name "/GPIO39") (class "Default")
      (node (ref "J2") (pin "11") (pinfunction "11_11") (pintype "passive"))
      (node (ref "U1") (pin "35") (pinfunction "MTCK/GPIO39/CLK_OUT3/SUBSPICS1_35") (pintype "passive"))
    )
    (net (code "50") (name "/GPIO40") (class "Default")
      (node (ref "J2") (pin "10") (pinfunction "10_10") (pintype "passive"))
      (node (ref "U1") (pin "36") (pinfunction "MTDO/GPIO40/CLK_OUT2_36") (pintype "passive"))
    )
    (net (code "51") (name "/GPIO41") (class "Default")
      (node (ref "J2") (pin "9") (pinfunction "9_9") (pintype "passive"))
      (node (ref "U1") (pin "37") (pinfunction "MTDI/GPIO41/CLK_OUT1_37") (pintype "passive"))
    )
    (net (code "52") (name "/GPIO42") (class "Default")
      (node (ref "J2") (pin "8") (pinfunction "8_8") (pintype "passive"))
      (node (ref "U1") (pin "38") (pinfunction "MTMS/GPIO42_38") (pintype "passive"))
    )
    (net (code "53") (name "/GPIO45") (class "Default")
      (node (ref "J2") (pin "5") (pinfunction "5_5") (pintype "passive"))
      (node (ref "U1") (pin "41") (pinfunction "GPIO45_41") (pintype "passive"))
    )
    (net (code "54") (name "/GPIO46") (class "Default")
      (node (ref "J2") (pin "4") (pinfunction "4_4") (pintype "passive"))
      (node (ref "U1") (pin "44") (pinfunction "GPIO46_44") (pintype "passive"))
    )
    (net (code "55") (name "/GPIO47") (class "Default")
      (node (ref "J2") (pin "23") (pinfunction "23_23") (pintype "passive"))
      (node (ref "U1") (pin "27") (pinfunction "GPIO47/SPICLK_P_DIFF/SUBSPICLK_P_DIFF_27") (pintype "passive"))
    )
    (net (code "56") (name "/GPIO48") (class "Default")
      (node (ref "J2") (pin "22") (pinfunction "22_22") (pintype "passive"))
      (node (ref "U1") (pin "30") (pinfunction "GPIO48/SPICLK_N_DIFF/SUBSPICLK_N_DIFF_30") (pintype "passive"))
    )
    (net (code "57") (name "/RTS_FTDI") (class "Default")
      (node (ref "Q1") (pin "2") (pinfunction "E_2") (pintype "passive"))
      (node (ref "R17") (pin "1") (pinfunction "1_1") (pintype "passive"))
      (node (ref "U2") (pin "19") (pinfunction "~{RTS}_19") (pintype "passive"))
    )
    (net (code "58") (name "/RXD_FTDI") (class "Default")
      (node (ref "R18") (pin "2") (pinfunction "2_2") (pintype "passive"))
      (node (ref "U2") (pin "1") (pinfunction "RXD_1") (pintype "passive"))
    )
    (net (code "59") (name "/TXD_FTDI") (class "Default")
      (node (ref "R19") (pin "2") (pinfunction "2_2") (pintype "passive"))
      (node (ref "U2") (pin "17") (pinfunction "TXD_17") (pintype "passive"))
    )
    (net (code "60") (name "/U0RXD") (class "Default")
      (node (ref "J2") (pin "6") (pinfunction "6_6") (pintype "passive"))
      (node (ref "R19") (pin "1") (pinfunction "1_1") (pintype "passive"))
      (node (ref "U1") (pin "40") (pinfunction "U0RXD/GPIO44/CLK_OUT2_40") (pintype "passive"))
    )
    (net (code "61") (name "/U0TXD") (class "Default")
      (node (ref "J2") (pin "7") (pinfunction "7_7") (pintype "passive"))
      (node (ref "R18") (pin "1") (pinfunction "1_1") (pintype "passive"))
      (node (ref "U1") (pin "39") (pinfunction "U0TXD/GPIO43/CLK_OUT1_39") (pintype "passive"))
    )
    (net (code "62") (name "/VBUS_SENSE") (class "Default")
      (node (ref "R13") (pin "2") (pinfunction "2_2") (pintype "passive"))
      (node (ref "R9") (pin "1") (pinfunction "1_1") (pintype "passive"))
      (node (ref "U2") (pin "16") (pinfunction "CBUS3_16") (pintype "passive"))
    )
    (net (code "63") (name "GND") (class "Default")
      (node (ref "C1") (pin "1") (pinfunction "1_1") (pintype "passive"))
      (node (ref "C10") (pin "1") (pinfunction "1_1") (pintype "passive"))
      (node (ref "C11") (pin "1") (pinfunction "1_1") (pintype "passive"))
      (node (ref "C12") (pin "1") (pinfunction "1_1") (pintype "passive"))
      (node (ref "C13") (pin "1") (pinfunction "1_1") (pintype "passive"))
      (node (ref "C14") (pin "1") (pinfunction "1_1") (pintype "passive"))
      (node (ref "C15") (pin "1") (pinfunction "1_1") (pintype "passive"))
      (node (ref "C16") (pin "1") (pinfunction "1_1") (pintype "passive"))
      (node (ref "C17") (pin "1") (pinfunction "1_1") (pintype "passive"))
      (node (ref "C2") (pin "1") (pinfunction "1_1") (pintype "passive"))
      (node (ref "C3") (pin "1") (pinfunction "1_1") (pintype "passive"))
      (node (ref "C4") (pin "1") (pinfunction "1_1") (pintype "passive"))
      (node (ref "C5") (pin "1") (pinfunction "1_1") (pintype "passive"))
      (node (ref "C6") (pin "1") (pinfunction "1_1") (pintype "passive"))
      (node (ref "C7") (pin "1") (pinfunction "1_1") (pintype "passive"))
      (node (ref "C8") (pin "1") (pinfunction "1_1") (pintype "passive"))
      (node (ref "C9") (pin "1") (pinfunction "1_1") (pintype "passive"))
      (node (ref "D1") (pin "1") (pinfunction "1_1") (pintype "passive"))
      (node (ref "D2") (pin "1") (pinfunction "1_1") (pintype "passive"))
      (node (ref "D3") (pin "1") (pinfunction "1_1") (pintype "passive"))
      (node (ref "D4") (pin "1") (pinfunction "1_1") (pintype "passive"))
      (node (ref "D6") (pin "1") (pinfunction "1_1") (pintype "passive"))
      (node (ref "D7") (pin "1") (pinfunction "1_1") (pintype "passive"))
      (node (ref "D8") (pin "1") (pinfunction "1_1") (pintype "passive"))
      (node (ref "J1") (pin "1") (pinfunction "1_1") (pintype "passive"))
      (node (ref "J1") (pin "23") (pinfunction "23_23") (pintype "passive"))
      (node (ref "J2") (pin "2") (pinfunction "2_2") (pintype "passive"))
      (node (ref "J2") (pin "24") (pinfunction "24_24") (pintype "passive"))
      (node (ref "J3") (pin "A1B12") (pinfunction "GND_A1B12_A1B12") (pintype "passive"))
      (node (ref "J3") (pin "B1A12") (pinfunction "GND_B1A12_B1A12") (pintype "passive"))
      (node (ref "J3") (pin "S1") (pinfunction "SHIELD_1_S1") (pintype "passive"))
      (node (ref "J3") (pin "S2") (pinfunction "SHIELD_2_S2") (pintype "passive"))
      (node (ref "J3") (pin "S3") (pinfunction "SHIELD_3_S3") (pintype "passive"))
      (node (ref "J3") (pin "S4") (pinfunction "SHIELD_4_S4") (pintype "passive"))
      (node (ref "J4") (pin "A1B12") (pinfunction "GND_A1B12_A1B12") (pintype "passive"))
      (node (ref "J4") (pin "B1A12") (pinfunction "GND_B1A12_B1A12") (pintype "passive"))
      (node (ref "J4") (pin "S1") (pinfunction "SHIELD_1_S1") (pintype "passive"))
      (node (ref "J4") (pin "S2") (pinfunction "SHIELD_2_S2") (pintype "passive"))
      (node (ref "J4") (pin "S3") (pinfunction "SHIELD_3_S3") (pintype "passive"))
      (node (ref "J4") (pin "S4") (pinfunction "SHIELD_4_S4") (pintype "passive"))
      (node (ref "R10") (pin "2") (pinfunction "2_2") (pintype "passive"))
      (node (ref "R11") (pin "1") (pinfunction "1_1") (pintype "passive"))
      (node (ref "R12") (pin "1") (pinfunction "1_1") (pintype "passive"))
      (node (ref "R13") (pin "1") (pinfunction "1_1") (pintype "passive"))
      (node (ref "R14") (pin "1") (pinfunction "1_1") (pintype "passive"))
      (node (ref "R15") (pin "1") (pinfunction "1_1") (pintype "passive"))
      (node (ref "SW1") (pin "3") (pinfunction "3_3") (pintype "passive"))
      (node (ref "SW1") (pin "4") (pinfunction "4_4") (pintype "passive"))
      (node (ref "SW2") (pin "3") (pinfunction "3_3") (pintype "passive"))
      (node (ref "SW2") (pin "4") (pinfunction "4_4") (pintype "passive"))
      (node (ref "U1") (pin "1") (pinfunction "GND_01_1") (pintype "passive"))
      (node (ref "U1") (pin "2") (pinfunction "GND_02_2") (pintype "passive"))
      (node (ref "U1") (pin "42") (pinfunction "GND_42_42") (pintype "passive"))
      (node (ref "U1") (pin "43") (pinfunction "GND_43_43") (pintype "passive"))
      (node (ref "U1") (pin "46") (pinfunction "GND_46_46") (pintype "passive"))
      (node (ref "U1") (pin "47") (pinfunction "GND_47_47") (pintype "passive"))
      (node (ref "U1") (pin "48") (pinfunction "GND_48_48") (pintype "passive"))
      (node (ref "U1") (pin "49") (pinfunction "GND_49_49") (pintype "passive"))
      (node (ref "U1") (pin "50") (pinfunction "GND_50_50") (pintype "passive"))
      (node (ref "U1") (pin "51") (pinfunction "GND_51_51") (pintype "passive"))
      (node (ref "U1") (pin "52") (pinfunction "GND_52_52") (pintype "passive"))
      (node (ref "U1") (pin "53") (pinfunction "GND_53_53") (pintype "passive"))
      (node (ref "U1") (pin "54") (pinfunction "GND_54_54") (pintype "passive"))
      (node (ref "U1") (pin "55") (pinfunction "GND_55_55") (pintype "passive"))
      (node (ref "U1") (pin "56") (pinfunction "GND_56_56") (pintype "passive"))
      (node (ref "U1") (pin "57") (pinfunction "GND_57_57") (pintype "passive"))
      (node (ref "U1") (pin "58") (pinfunction "GND_58_58") (pintype "passive"))
      (node (ref "U1") (pin "59") (pinfunction "GND_59_59") (pintype "passive"))
      (node (ref "U1") (pin "60") (pinfunction "GND_60_60") (pintype "passive"))
      (node (ref "U1") (pin "61") (pinfunction "GND_61_61") (pintype "passive"))
      (node (ref "U1") (pin "62") (pinfunction "GND_62_62") (pintype "passive"))
      (node (ref "U1") (pin "63") (pinfunction "GND_63_63") (pintype "passive"))
      (node (ref "U1") (pin "64") (pinfunction "GND_64_64") (pintype "passive"))
      (node (ref "U1") (pin "65") (pinfunction "GND_65_65") (pintype "passive"))
      (node (ref "U1") (pin "66") (pinfunction "GND_66_66") (pintype "passive"))
      (node (ref "U1") (pin "67") (pinfunction "GND_67_67") (pintype "passive"))
      (node (ref "U1") (pin "68") (pinfunction "GND_68_68") (pintype "passive"))
      (node (ref "U1") (pin "69") (pinfunction "GND_69_69") (pintype "passive"))
      (node (ref "U1") (pin "70") (pinfunction "GND_70_70") (pintype "passive"))
      (node (ref "U1") (pin "71") (pinfunction "GND_71_71") (pintype "passive"))
      (node (ref "U1") (pin "72") (pinfunction "GND_72_72") (pintype "passive"))
      (node (ref "U1") (pin "73") (pinfunction "GND_73_73") (pintype "passive"))
      (node (ref "U2") (pin "13") (pinfunction "GND_13") (pintype "passive"))
      (node (ref "U2") (pin "21") (pinfunction "GND_21") (pintype "passive"))
      (node (ref "U2") (pin "3") (pinfunction "GND_3") (pintype "passive"))
      (node (ref "U3") (pin "2") (pinfunction "GND_2") (pintype "power_in"))
      (node (ref "U3") (pin "4") (pinfunction "GND_4") (pintype "power_in"))
    )
    (net (code "64") (name "Net-(D4-Pad2)") (class "Default")
      (node (ref "D4") (pin "2") (pinfunction "2_2") (pintype "passive"))
      (node (ref "R5") (pin "1") (pinfunction "1_1") (pintype "passive"))
    )
    (net (code "65") (name "Net-(D5-Pad2)") (class "Default")
      (node (ref "D5") (pin "2") (pinfunction "2_2") (pintype "passive"))
      (node (ref "R6") (pin "1") (pinfunction "1_1") (pintype "passive"))
    )
    (net (code "66") (name "Net-(J3-CC1)") (class "Default")
      (node (ref "J3") (pin "A5") (pinfunction "CC1_A5") (pintype "passive"))
      (node (ref "R12") (pin "2") (pinfunction "2_2") (pintype "passive"))
    )
    (net (code "67") (name "Net-(J3-CC2)") (class "Default")
      (node (ref "J3") (pin "B5") (pinfunction "CC2_B5") (pintype "passive"))
      (node (ref "R11") (pin "2") (pinfunction "2_2") (pintype "passive"))
    )
    (net (code "68") (name "Net-(J4-CC1)") (class "Default")
      (node (ref "J4") (pin "A5") (pinfunction "CC1_A5") (pintype "passive"))
      (node (ref "R15") (pin "2") (pinfunction "2_2") (pintype "passive"))
    )
    (net (code "69") (name "Net-(J4-CC2)") (class "Default")
      (node (ref "J4") (pin "B5") (pinfunction "CC2_B5") (pintype "passive"))
      (node (ref "R14") (pin "2") (pinfunction "2_2") (pintype "passive"))
    )
    (net (code "70") (name "Net-(Q1-B)") (class "Default")
      (node (ref "Q1") (pin "1") (pinfunction "B_1") (pintype "passive"))
      (node (ref "R16") (pin "2") (pinfunction "2_2") (pintype "passive"))
    )
    (net (code "71") (name "Net-(Q2-B)") (class "Default")
      (node (ref "Q2") (pin "1") (pinfunction "B_1") (pintype "passive"))
      (node (ref "R17") (pin "2") (pinfunction "2_2") (pintype "passive"))
    )
    (net (code "72") (name "Net-(U2-CBUS0)") (class "Default")
      (node (ref "R10") (pin "1") (pinfunction "1_1") (pintype "passive"))
      (node (ref "U2") (pin "15") (pinfunction "CBUS0_15") (pintype "passive"))
    )
    (net (code "73") (name "Net-(U2-~{RESET})") (class "Default")
      (node (ref "C7") (pin "2") (pinfunction "2_2") (pintype "passive"))
      (node (ref "R8") (pin "2") (pinfunction "2_2") (pintype "passive"))
      (node (ref "U2") (pin "11") (pinfunction "~{RESET}_11") (pintype "passive"))
    )
    (net (code "74") (name "unconnected-(J1-Pad24)") (class "Default")
      (node (ref "J1") (pin "24") (pinfunction "24_24") (pintype "passive+no_connect"))
    )
    (net (code "75") (name "unconnected-(J3-SBU1-PadA8)") (class "Default")
      (node (ref "J3") (pin "A8") (pinfunction "SBU1_A8") (pintype "passive+no_connect"))
    )
    (net (code "76") (name "unconnected-(J3-SBU2-PadB8)") (class "Default")
      (node (ref "J3") (pin "B8") (pinfunction "SBU2_B8") (pintype "passive+no_connect"))
    )
    (net (code "77") (name "unconnected-(J4-SBU1-PadA8)") (class "Default")
      (node (ref "J4") (pin "A8") (pinfunction "SBU1_A8") (pintype "passive+no_connect"))
    )
    (net (code "78") (name "unconnected-(J4-SBU2-PadB8)") (class "Default")
      (node (ref "J4") (pin "B8") (pinfunction "SBU2_B8") (pintype "passive+no_connect"))
    )
    (net (code "79") (name "unconnected-(U2-CBUS1-Pad14)") (class "Default")
      (node (ref "U2") (pin "14") (pinfunction "CBUS1_14") (pintype "passive+no_connect"))
    )
    (net (code "80") (name "unconnected-(U2-CBUS2-Pad7)") (class "Default")
      (node (ref "U2") (pin "7") (pinfunction "CBUS2_7") (pintype "passive+no_connect"))
    )
    (net (code "81") (name "unconnected-(U2-~{CTS}-Pad6)") (class "Default")
      (node (ref "U2") (pin "6") (pinfunction "~{CTS}_6") (pintype "passive+no_connect"))
    )
    (net (code "82") (name "unconnected-(U2-~{DCD}-Pad5)") (class "Default")
      (node (ref "U2") (pin "5") (pinfunction "~{DCD}_5") (pintype "passive+no_connect"))
    )
    (net (code "83") (name "unconnected-(U2-~{DSR}-Pad4)") (class "Default")
      (node (ref "U2") (pin "4") (pinfunction "~{DSR}_4") (pintype "passive+no_connect"))
    )
    (net (code "84") (name "unconnected-(U2-~{RI}-Pad2)") (class "Default")
      (node (ref "U2") (pin "2") (pinfunction "~{RI}_2") (pintype "passive+no_connect"))
    )
  )
)
